# ptt_interface.net
KiCad netlist of a schematic drawn in EAGLE
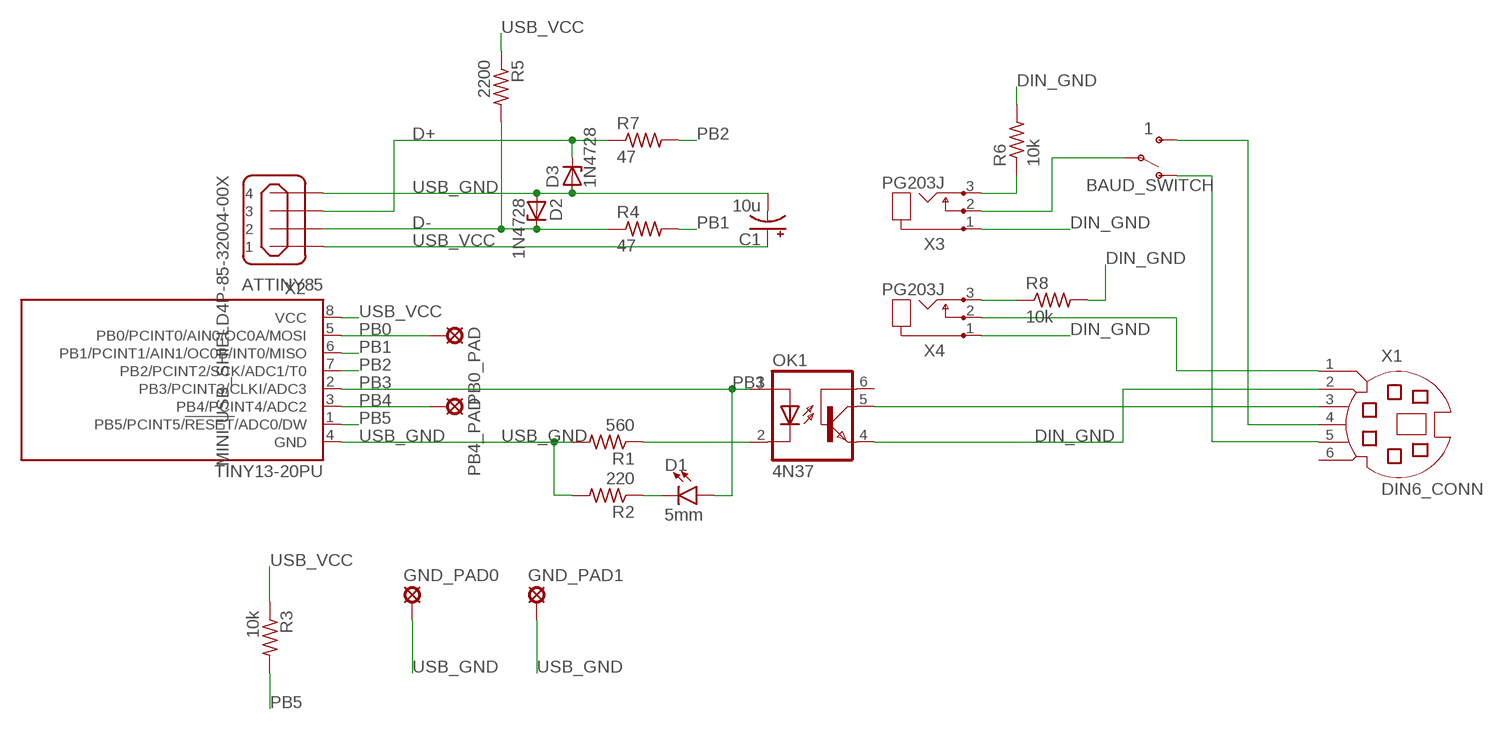
[diagram p0: schematic, sheet 1]

(export (version "E")
  (design (tool "Eeschema 10.0.6"))
  (components
    (comp (ref "ATTINY85")
      (value "TINY13-20PU")
      (footprint "eagle-import:DIL08")
      (fields (field (name "MPN") "ATTINY13-20PU"))
      (libsource (lib "eagle-import") (part "TINY13PU-20"))
    )
    (comp (ref "BAUD_SWITCH")
      (value "1")
      (footprint "eagle-import:SWITCH_SPDT_PTH_15X5.6MM")
      (libsource (lib "eagle-import") (part "SWITCH-SPDT"))
    )
    (comp (ref "C1")
      (value "10u")
      (footprint "eagle-import:E2,5-5")
      (libsource (lib "eagle-import") (part "CPOL-USE2.5-5"))
    )
    (comp (ref "D1")
      (value "5mm")
      (footprint "eagle-import:LED_5MM")
      (libsource (lib "eagle-import") (part "LED5MM"))
    )
    (comp (ref "D2")
      (value "1N4728")
      (footprint "eagle-import:DO41Z10")
      (libsource (lib "eagle-import") (part "1N4728"))
    )
    (comp (ref "D3")
      (value "1N4728")
      (footprint "eagle-import:DO41Z10")
      (libsource (lib "eagle-import") (part "1N4728"))
    )
    (comp (ref "GND_PAD0")
      (value "LSP11")
      (footprint "eagle-import:LSP11")
      (libsource (lib "eagle-import") (part "LSP11"))
    )
    (comp (ref "GND_PAD1")
      (value "LSP11")
      (footprint "eagle-import:LSP11")
      (libsource (lib "eagle-import") (part "LSP11"))
    )
    (comp (ref "OK1")
      (value "4N37")
      (footprint "eagle-import:DIL06")
      (fields (field (name "MF") "FAIRCHILD SEMICONDUCTOR"))
      (libsource (lib "eagle-import") (part "4N37"))
    )
    (comp (ref "PB0_PAD")
      (value "LSP11")
      (footprint "eagle-import:LSP11")
      (libsource (lib "eagle-import") (part "LSP11"))
    )
    (comp (ref "PB4_PAD")
      (value "LSP11")
      (footprint "eagle-import:LSP11")
      (libsource (lib "eagle-import") (part "LSP11"))
    )
    (comp (ref "R1")
      (value "560")
      (footprint "eagle-import:0207_10")
      (libsource (lib "eagle-import") (part "R-US_0207/10"))
    )
    (comp (ref "R2")
      (value "220")
      (footprint "eagle-import:0207_10")
      (libsource (lib "eagle-import") (part "R-US_0207/10"))
    )
    (comp (ref "R3")
      (value "10k")
      (footprint "eagle-import:0207_10")
      (libsource (lib "eagle-import") (part "R-US_0207/10"))
    )
    (comp (ref "R4")
      (value "47")
      (footprint "eagle-import:0207_10")
      (libsource (lib "eagle-import") (part "R-US_0207/10"))
    )
    (comp (ref "R5")
      (value "2200")
      (footprint "eagle-import:0207_10")
      (libsource (lib "eagle-import") (part "R-US_0207/10"))
    )
    (comp (ref "R6")
      (value "10k")
      (footprint "eagle-import:0207_10")
      (libsource (lib "eagle-import") (part "R-US_0207/10"))
    )
    (comp (ref "R7")
      (value "47")
      (footprint "eagle-import:0207_10")
      (libsource (lib "eagle-import") (part "R-US_0207/10"))
    )
    (comp (ref "R8")
      (value "10k")
      (footprint "eagle-import:0207_10")
      (libsource (lib "eagle-import") (part "R-US_0207/10"))
    )
    (comp (ref "X1")
      (value "DIN6_CONN")
      (footprint "eagle-import:MDIN06SS")
      (libsource (lib "eagle-import") (part "MD06SS"))
    )
    (comp (ref "X2")
      (value "MINI-USB_SHIELD4P-85-32004-00X")
      (footprint "eagle-import:85-32004-00X")
      (libsource (lib "eagle-import") (part "MINI-USB_SHIELD4P-85-32004-00X"))
    )
    (comp (ref "X3")
      (value "PG203J")
      (footprint "eagle-import:PG203J")
      (libsource (lib "eagle-import") (part "PG203J"))
    )
    (comp (ref "X4")
      (value "PG203J")
      (footprint "eagle-import:PG203J")
      (libsource (lib "eagle-import") (part "PG203J"))
    )
  )
  (nets
    (net (code "1") (name "/D+") (class "Default")
      (node (ref "D3") (pin "C") (pinfunction "C_C") (pintype "passive"))
      (node (ref "R7") (pin "1") (pinfunction "1_1") (pintype "passive"))
      (node (ref "X2") (pin "3") (pinfunction "3_3") (pintype "passive"))
    )
    (net (code "2") (name "/D-") (class "Default")
      (node (ref "D2") (pin "C") (pinfunction "C_C") (pintype "passive"))
      (node (ref "R4") (pin "1") (pinfunction "1_1") (pintype "passive"))
      (node (ref "R5") (pin "2") (pinfunction "2_2") (pintype "passive"))
      (node (ref "X2") (pin "2") (pinfunction "2_2") (pintype "passive"))
    )
    (net (code "3") (name "/DIN_GND") (class "Default")
      (node (ref "OK1") (pin "4") (pinfunction "EMI_4") (pintype "passive"))
      (node (ref "R6") (pin "2") (pinfunction "2_2") (pintype "passive"))
      (node (ref "R8") (pin "2") (pinfunction "2_2") (pintype "passive"))
      (node (ref "X1") (pin "2") (pinfunction "2_2") (pintype "passive"))
      (node (ref "X3") (pin "1") (pinfunction "1_1") (pintype "passive"))
      (node (ref "X4") (pin "1") (pinfunction "1_1") (pintype "passive"))
    )
    (net (code "4") (name "/PB0") (class "Default")
      (node (ref "ATTINY85") (pin "5") (pinfunction "PB0/PCINT0/AIN0/OC0A/MOSI_5") (pintype "bidirectional"))
      (node (ref "PB0_PAD") (pin "MP") (pinfunction "MP_MP") (pintype "passive"))
    )
    (net (code "5") (name "/PB1") (class "Default")
      (node (ref "ATTINY85") (pin "6") (pinfunction "PB1/PCINT1/AIN1/OC0B/INT0/MISO_6") (pintype "bidirectional"))
      (node (ref "R4") (pin "2") (pinfunction "2_2") (pintype "passive"))
    )
    (net (code "6") (name "/PB2") (class "Default")
      (node (ref "ATTINY85") (pin "7") (pinfunction "PB2/PCINT2/SCK/ADC1/T0_7") (pintype "bidirectional"))
      (node (ref "R7") (pin "2") (pinfunction "2_2") (pintype "passive"))
    )
    (net (code "7") (name "/PB3") (class "Default")
      (node (ref "ATTINY85") (pin "2") (pinfunction "PB3/PCINT3/CLKI/ADC3_2") (pintype "bidirectional"))
      (node (ref "D1") (pin "A") (pinfunction "A_A") (pintype "passive"))
      (node (ref "OK1") (pin "1") (pinfunction "A_1") (pintype "passive"))
    )
    (net (code "8") (name "/PB4") (class "Default")
      (node (ref "ATTINY85") (pin "3") (pinfunction "PB4/PCINT4/ADC2_3") (pintype "bidirectional"))
      (node (ref "PB4_PAD") (pin "MP") (pinfunction "MP_MP") (pintype "passive"))
    )
    (net (code "9") (name "/PB5") (class "Default")
      (node (ref "ATTINY85") (pin "1") (pinfunction "PB5/PCINT5/~{RESET}/ADC0/DW_1") (pintype "bidirectional"))
      (node (ref "R3") (pin "2") (pinfunction "2_2") (pintype "passive"))
    )
    (net (code "10") (name "/USB_GND") (class "Default")
      (node (ref "ATTINY85") (pin "4") (pinfunction "GND_4") (pintype "power_in"))
      (node (ref "C1") (pin "-") (pinfunction "-_-") (pintype "passive"))
      (node (ref "D2") (pin "A") (pinfunction "A_A") (pintype "passive"))
      (node (ref "D3") (pin "A") (pinfunction "A_A") (pintype "passive"))
      (node (ref "GND_PAD0") (pin "MP") (pinfunction "MP_MP") (pintype "passive"))
      (node (ref "GND_PAD1") (pin "MP") (pinfunction "MP_MP") (pintype "passive"))
      (node (ref "R1") (pin "2") (pinfunction "2_2") (pintype "passive"))
      (node (ref "R2") (pin "2") (pinfunction "2_2") (pintype "passive"))
      (node (ref "X2") (pin "4") (pinfunction "4_4") (pintype "passive"))
    )
    (net (code "11") (name "/USB_VCC") (class "Default")
      (node (ref "ATTINY85") (pin "8") (pinfunction "VCC_8") (pintype "power_in"))
      (node (ref "C1") (pin "+") (pinfunction "+_+") (pintype "passive"))
      (node (ref "R3") (pin "1") (pinfunction "1_1") (pintype "passive"))
      (node (ref "R5") (pin "1") (pinfunction "1_1") (pintype "passive"))
      (node (ref "X2") (pin "1") (pinfunction "1_1") (pintype "passive"))
    )
    (net (code "12") (name "Net-(BAUD_SWITCH-O)") (class "Default")
      (node (ref "BAUD_SWITCH") (pin "1") (pinfunction "O_1") (pintype "passive"))
      (node (ref "X1") (pin "5") (pinfunction "5_5") (pintype "passive"))
    )
    (net (code "13") (name "Net-(BAUD_SWITCH-P)") (class "Default")
      (node (ref "BAUD_SWITCH") (pin "2") (pinfunction "P_2") (pintype "passive"))
      (node (ref "X3") (pin "2") (pinfunction "3_2") (pintype "passive"))
    )
    (net (code "14") (name "Net-(BAUD_SWITCH-S)") (class "Default")
      (node (ref "BAUD_SWITCH") (pin "3") (pinfunction "S_3") (pintype "passive"))
      (node (ref "X1") (pin "4") (pinfunction "4_4") (pintype "passive"))
    )
    (net (code "15") (name "Net-(D1-C)") (class "Default")
      (node (ref "D1") (pin "K") (pinfunction "C_K") (pintype "passive"))
      (node (ref "R2") (pin "1") (pinfunction "1_1") (pintype "passive"))
    )
    (net (code "16") (name "Net-(OK1-C)") (class "Default")
      (node (ref "OK1") (pin "2") (pinfunction "C_2") (pintype "passive"))
      (node (ref "R1") (pin "1") (pinfunction "1_1") (pintype "passive"))
    )
    (net (code "17") (name "Net-(OK1-COL)") (class "Default")
      (node (ref "OK1") (pin "5") (pinfunction "COL_5") (pintype "passive"))
      (node (ref "X1") (pin "3") (pinfunction "3_3") (pintype "passive"))
    )
    (net (code "18") (name "Net-(X3-2)") (class "Default")
      (node (ref "R6") (pin "1") (pinfunction "1_1") (pintype "passive"))
      (node (ref "X3") (pin "3") (pinfunction "2_3") (pintype "passive"))
    )
    (net (code "19") (name "Net-(X4-2)") (class "Default")
      (node (ref "R8") (pin "1") (pinfunction "1_1") (pintype "passive"))
      (node (ref "X4") (pin "3") (pinfunction "2_3") (pintype "passive"))
    )
    (net (code "20") (name "Net-(X4-3)") (class "Default")
      (node (ref "X1") (pin "1") (pinfunction "1_1") (pintype "passive"))
      (node (ref "X4") (pin "2") (pinfunction "3_2") (pintype "passive"))
    )
    (net (code "21") (name "unconnected-(OK1-BAS-Pad6)") (class "Default")
      (node (ref "OK1") (pin "6") (pinfunction "BAS_6") (pintype "passive"))
    )
    (net (code "22") (name "unconnected-(X1-Pad6)") (class "Default")
      (node (ref "X1") (pin "6") (pinfunction "6_6") (pintype "passive"))
    )
  )
)
